# Adafruit_Motor_HAT_rev_A.net
KiCad netlist of a schematic drawn in EAGLE
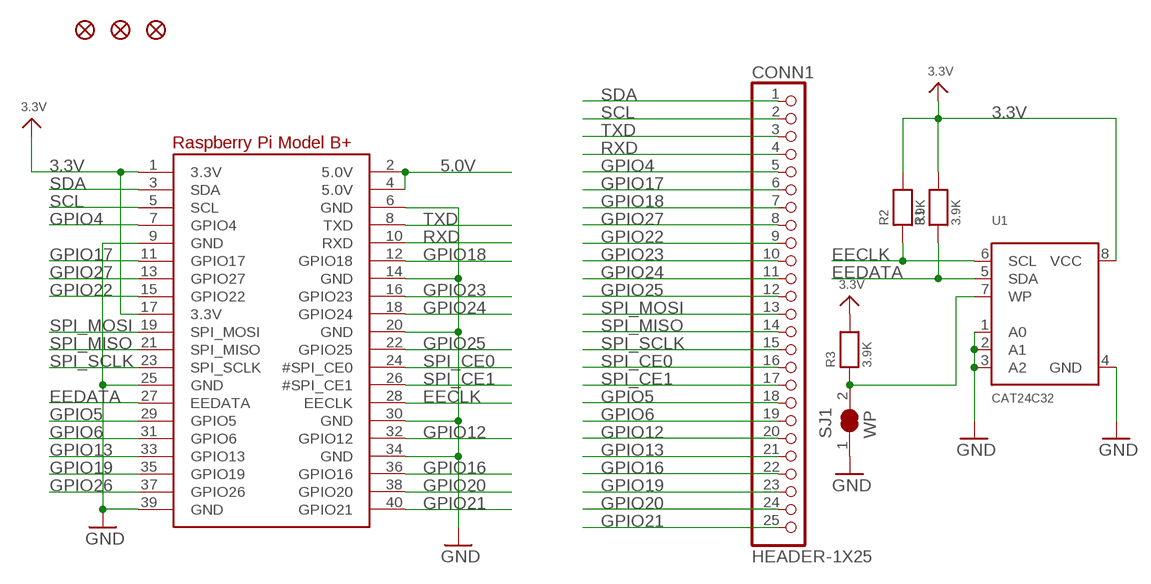
[diagram p0: schematic, sheet 1]
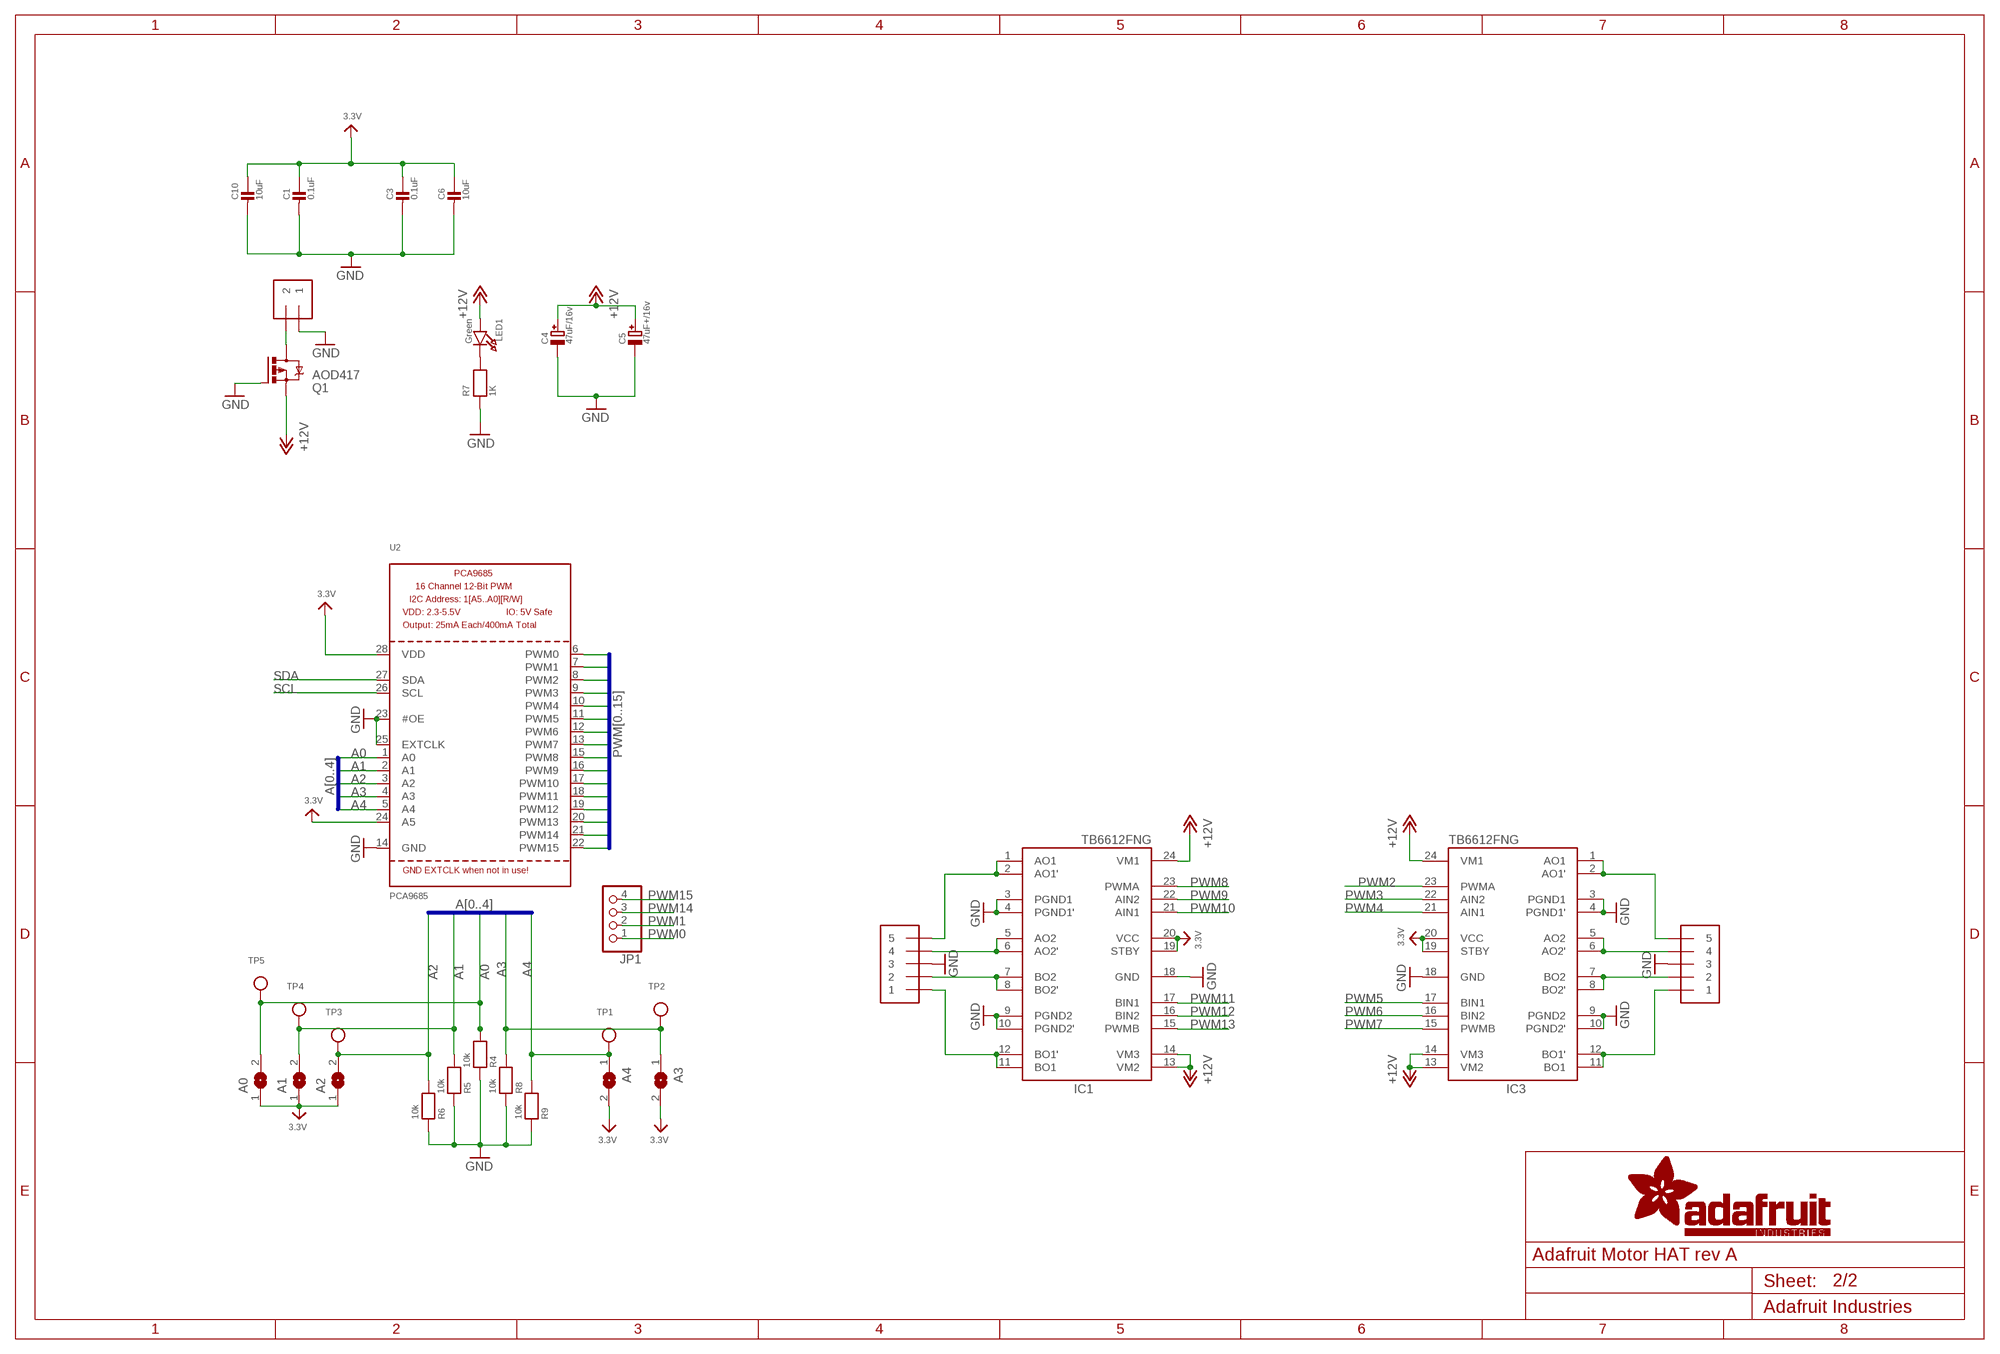
[diagram p1: schematic, sheet 2]

(export (version "E")
  (design (tool "Eeschema 10.0.6"))
  (components
    (comp (ref "CONN1")
      (value "HEADER-1X25")
      (footprint "eagle-import:1X25_ROUND_70MIL")
      (libsource (lib "eagle-import") (part "HEADER-1X25"))
    )
    (comp (ref "FID1")
      (value "FIDUCIAL\"\"")
      (footprint "eagle-import:FIDUCIAL_1MM")
      (libsource (lib "eagle-import") (part "FIDUCIAL{dblquote}{dblquote}"))
    )
    (comp (ref "FID2")
      (value "FIDUCIAL\"\"")
      (footprint "eagle-import:FIDUCIAL_1MM")
      (libsource (lib "eagle-import") (part "FIDUCIAL{dblquote}{dblquote}"))
    )
    (comp (ref "FID3")
      (value "FIDUCIAL\"\"")
      (footprint "eagle-import:FIDUCIAL_1MM")
      (libsource (lib "eagle-import") (part "FIDUCIAL{dblquote}{dblquote}"))
    )
    (comp (ref "R1")
      (value "3.9K")
      (footprint "eagle-import:0805-NO")
      (libsource (lib "eagle-import") (part "RESISTOR0805_NOOUTLINE"))
    )
    (comp (ref "R2")
      (value "3.9K")
      (footprint "eagle-import:0805-NO")
      (libsource (lib "eagle-import") (part "RESISTOR0805_NOOUTLINE"))
    )
    (comp (ref "R3")
      (value "3.9K")
      (footprint "eagle-import:0805-NO")
      (libsource (lib "eagle-import") (part "RESISTOR0805_NOOUTLINE"))
    )
    (comp (ref "RPI1")
      (value "RASPBERRYPI_BPLUS_HATSLOTS")
      (footprint "eagle-import:PI_HAT_SLOTS")
      (libsource (lib "eagle-import") (part "RASPBERRYPI_BPLUS_HATSLOTS"))
    )
    (comp (ref "SJ1")
      (value "WP")
      (footprint "eagle-import:SOLDERJUMPER_CLOSEDWIRE")
      (libsource (lib "eagle-import") (part "SOLDERJUMPER_CLOSED"))
    )
    (comp (ref "U1")
      (value "CAT24C32")
      (footprint "eagle-import:SOIC8_150MIL")
      (libsource (lib "eagle-import") (part "EEPROM_I2C_SOIC8_GENERIC"))
    )
    (comp (ref "A0")
      (value "SOLDERJUMPERREFLOW_NOPASTE")
      (footprint "eagle-import:SOLDERJUMPER_REFLOW_NOPASTE")
      (libsource (lib "eagle-import") (part "SOLDERJUMPERREFLOW_NOPASTE"))
    )
    (comp (ref "A1")
      (value "SOLDERJUMPERREFLOW_NOPASTE")
      (footprint "eagle-import:SOLDERJUMPER_REFLOW_NOPASTE")
      (libsource (lib "eagle-import") (part "SOLDERJUMPERREFLOW_NOPASTE"))
    )
    (comp (ref "A2")
      (value "SOLDERJUMPERREFLOW_NOPASTE")
      (footprint "eagle-import:SOLDERJUMPER_REFLOW_NOPASTE")
      (libsource (lib "eagle-import") (part "SOLDERJUMPERREFLOW_NOPASTE"))
    )
    (comp (ref "A3")
      (value "SOLDERJUMPERREFLOW_NOPASTE")
      (footprint "eagle-import:SOLDERJUMPER_REFLOW_NOPASTE")
      (libsource (lib "eagle-import") (part "SOLDERJUMPERREFLOW_NOPASTE"))
    )
    (comp (ref "A4")
      (value "SOLDERJUMPERREFLOW_NOPASTE")
      (footprint "eagle-import:SOLDERJUMPER_REFLOW_NOPASTE")
      (libsource (lib "eagle-import") (part "SOLDERJUMPERREFLOW_NOPASTE"))
    )
    (comp (ref "C1")
      (value "0.1uF")
      (footprint "eagle-import:0805-NO")
      (libsource (lib "eagle-import") (part "CAP_CERAMIC0805-NOOUTLINE"))
    )
    (comp (ref "C3")
      (value "0.1uF")
      (footprint "eagle-import:0805-NO")
      (libsource (lib "eagle-import") (part "CAP_CERAMIC0805-NOOUTLINE"))
    )
    (comp (ref "C4")
      (value "47uF/16v")
      (footprint "eagle-import:PANASONIC_C")
      (libsource (lib "eagle-import") (part "CAP_ELECTROLYTICPANASONIC_C"))
    )
    (comp (ref "C5")
      (value "47uF+/16v")
      (footprint "eagle-import:PANASONIC_C")
      (libsource (lib "eagle-import") (part "CAP_ELECTROLYTICPANASONIC_C"))
    )
    (comp (ref "C6")
      (value "10uF")
      (footprint "eagle-import:0805-NO")
      (libsource (lib "eagle-import") (part "CAP_CERAMIC0805-NOOUTLINE"))
    )
    (comp (ref "C10")
      (value "10uF")
      (footprint "eagle-import:0805-NO")
      (libsource (lib "eagle-import") (part "CAP_CERAMIC0805-NOOUTLINE"))
    )
    (comp (ref "IC1")
      (value "TB6612FNG")
      (footprint "eagle-import:SSOP24")
      (libsource (lib "eagle-import") (part "TB6612FNG"))
    )
    (comp (ref "IC3")
      (value "TB6612FNG")
      (footprint "eagle-import:SSOP24")
      (libsource (lib "eagle-import") (part "TB6612FNG"))
    )
    (comp (ref "J1")
      (value "1X5")
      (footprint "eagle-import:1X05-3.5MM")
      (libsource (lib "eagle-import") (part "1X5"))
    )
    (comp (ref "J3")
      (value "1X5")
      (footprint "eagle-import:1X05-3.5MM")
      (libsource (lib "eagle-import") (part "1X5"))
    )
    (comp (ref "JP1")
      (value "HEADER-1X476MIL")
      (footprint "eagle-import:1X04_ROUND_76")
      (libsource (lib "eagle-import") (part "HEADER-1X476MIL"))
    )
    (comp (ref "LED1")
      (value "Green")
      (footprint "eagle-import:CHIPLED_0805_NOOUTLINE")
      (libsource (lib "eagle-import") (part "LED0805_NOOUTLINE"))
    )
    (comp (ref "MPOWER")
      (value "1X2-3.5MM")
      (footprint "eagle-import:1X2-3.5MM")
      (libsource (lib "eagle-import") (part "1X2-3.5MM"))
    )
    (comp (ref "Q1")
      (value "AOD417")
      (footprint "eagle-import:D-PAK_TO252AA")
      (libsource (lib "eagle-import") (part "IRF?5305R"))
    )
    (comp (ref "R4")
      (value "10k")
      (footprint "eagle-import:0805-NO")
      (libsource (lib "eagle-import") (part "RESISTOR0805_NOOUTLINE"))
    )
    (comp (ref "R5")
      (value "10k")
      (footprint "eagle-import:0805-NO")
      (libsource (lib "eagle-import") (part "RESISTOR0805_NOOUTLINE"))
    )
    (comp (ref "R6")
      (value "10k")
      (footprint "eagle-import:0805-NO")
      (libsource (lib "eagle-import") (part "RESISTOR0805_NOOUTLINE"))
    )
    (comp (ref "R7")
      (value "1K")
      (footprint "eagle-import:0805-NO")
      (libsource (lib "eagle-import") (part "RESISTOR0805_NOOUTLINE"))
    )
    (comp (ref "R8")
      (value "10k")
      (footprint "eagle-import:0805-NO")
      (libsource (lib "eagle-import") (part "RESISTOR0805_NOOUTLINE"))
    )
    (comp (ref "R9")
      (value "10k")
      (footprint "eagle-import:0805-NO")
      (libsource (lib "eagle-import") (part "RESISTOR0805_NOOUTLINE"))
    )
    (comp (ref "TP1")
      (value "TESTPOINTROUND2MM")
      (footprint "eagle-import:TESTPOINT_ROUND_2MM")
      (libsource (lib "eagle-import") (part "TESTPOINTROUND2MM"))
    )
    (comp (ref "TP2")
      (value "TESTPOINTROUND2MM")
      (footprint "eagle-import:TESTPOINT_ROUND_2MM")
      (libsource (lib "eagle-import") (part "TESTPOINTROUND2MM"))
    )
    (comp (ref "TP3")
      (value "TESTPOINTROUND2MM")
      (footprint "eagle-import:TESTPOINT_ROUND_2MM")
      (libsource (lib "eagle-import") (part "TESTPOINTROUND2MM"))
    )
    (comp (ref "TP4")
      (value "TESTPOINTROUND2MM")
      (footprint "eagle-import:TESTPOINT_ROUND_2MM")
      (libsource (lib "eagle-import") (part "TESTPOINTROUND2MM"))
    )
    (comp (ref "TP5")
      (value "TESTPOINTROUND2MM")
      (footprint "eagle-import:TESTPOINT_ROUND_2MM")
      (libsource (lib "eagle-import") (part "TESTPOINTROUND2MM"))
    )
    (comp (ref "U2")
      (value "PCA9685")
      (footprint "eagle-import:TSSOP28")
      (libsource (lib "eagle-import") (part "PCA9685"))
    )
  )
  (nets
    (net (code "1") (name "+12V") (class "Default")
      (node (ref "C4") (pin "+") (pinfunction "+_+") (pintype "passive"))
      (node (ref "C5") (pin "+") (pinfunction "+_+") (pintype "passive"))
      (node (ref "IC1") (pin "13") (pinfunction "VM2_13") (pintype "power_in"))
      (node (ref "IC1") (pin "14") (pinfunction "VM3_14") (pintype "power_in"))
      (node (ref "IC1") (pin "24") (pinfunction "VM1_24") (pintype "power_in"))
      (node (ref "IC3") (pin "13") (pinfunction "VM2_13") (pintype "power_in"))
      (node (ref "IC3") (pin "14") (pinfunction "VM3_14") (pintype "power_in"))
      (node (ref "IC3") (pin "24") (pinfunction "VM1_24") (pintype "power_in"))
      (node (ref "LED1") (pin "A") (pinfunction "A_A") (pintype "passive"))
      (node (ref "Q1") (pin "3") (pinfunction "S_3") (pintype "passive"))
    )
    (net (code "4") (name "3.3V") (class "Default")
      (node (ref "A0") (pin "1") (pinfunction "1_1") (pintype "passive"))
      (node (ref "A1") (pin "1") (pinfunction "1_1") (pintype "passive"))
      (node (ref "A2") (pin "1") (pinfunction "1_1") (pintype "passive"))
      (node (ref "A3") (pin "2") (pinfunction "2_2") (pintype "passive"))
      (node (ref "A4") (pin "2") (pinfunction "2_2") (pintype "passive"))
      (node (ref "C1") (pin "1") (pinfunction "1_1") (pintype "passive"))
      (node (ref "C10") (pin "1") (pinfunction "1_1") (pintype "passive"))
      (node (ref "C3") (pin "1") (pinfunction "1_1") (pintype "passive"))
      (node (ref "C6") (pin "1") (pinfunction "1_1") (pintype "passive"))
      (node (ref "IC1") (pin "19") (pinfunction "STBY_19") (pintype "input"))
      (node (ref "IC1") (pin "20") (pinfunction "VCC_20") (pintype "power_in"))
      (node (ref "IC3") (pin "19") (pinfunction "STBY_19") (pintype "input"))
      (node (ref "IC3") (pin "20") (pinfunction "VCC_20") (pintype "power_in"))
      (node (ref "R1") (pin "2") (pinfunction "2_2") (pintype "passive"))
      (node (ref "R2") (pin "2") (pinfunction "2_2") (pintype "passive"))
      (node (ref "R3") (pin "2") (pinfunction "2_2") (pintype "passive"))
      (node (ref "RPI1") (pin "1") (pinfunction "3.3V_1") (pintype "power_in"))
      (node (ref "RPI1") (pin "17") (pinfunction "3.3V_17") (pintype "power_in"))
      (node (ref "U1") (pin "8") (pinfunction "VCC_8") (pintype "power_in"))
      (node (ref "U2") (pin "24") (pinfunction "A5_24") (pintype "bidirectional"))
      (node (ref "U2") (pin "28") (pinfunction "VDD_28") (pintype "power_in"))
    )
    (net (code "5") (name "5.0V") (class "Default")
      (node (ref "RPI1") (pin "2") (pinfunction "5.0V_2") (pintype "power_in"))
      (node (ref "RPI1") (pin "4") (pinfunction "5.0V_4") (pintype "power_in"))
    )
    (net (code "6") (name "A0") (class "Default")
      (node (ref "A0") (pin "2") (pinfunction "2_2") (pintype "passive"))
      (node (ref "R4") (pin "2") (pinfunction "2_2") (pintype "passive"))
      (node (ref "TP5") (pin "P$1") (pinfunction "P$1_P$1") (pintype "bidirectional"))
      (node (ref "U2") (pin "1") (pinfunction "A0_1") (pintype "bidirectional"))
    )
    (net (code "7") (name "A1") (class "Default")
      (node (ref "A1") (pin "2") (pinfunction "2_2") (pintype "passive"))
      (node (ref "R5") (pin "2") (pinfunction "2_2") (pintype "passive"))
      (node (ref "TP4") (pin "P$1") (pinfunction "P$1_P$1") (pintype "bidirectional"))
      (node (ref "U2") (pin "2") (pinfunction "A1_2") (pintype "bidirectional"))
    )
    (net (code "8") (name "A2") (class "Default")
      (node (ref "A2") (pin "2") (pinfunction "2_2") (pintype "passive"))
      (node (ref "R6") (pin "2") (pinfunction "2_2") (pintype "passive"))
      (node (ref "TP3") (pin "P$1") (pinfunction "P$1_P$1") (pintype "bidirectional"))
      (node (ref "U2") (pin "3") (pinfunction "A2_3") (pintype "bidirectional"))
    )
    (net (code "9") (name "A3") (class "Default")
      (node (ref "A3") (pin "1") (pinfunction "1_1") (pintype "passive"))
      (node (ref "R8") (pin "2") (pinfunction "2_2") (pintype "passive"))
      (node (ref "TP2") (pin "P$1") (pinfunction "P$1_P$1") (pintype "bidirectional"))
      (node (ref "U2") (pin "4") (pinfunction "A3_4") (pintype "bidirectional"))
    )
    (net (code "10") (name "A4") (class "Default")
      (node (ref "A4") (pin "1") (pinfunction "1_1") (pintype "passive"))
      (node (ref "R9") (pin "2") (pinfunction "2_2") (pintype "passive"))
      (node (ref "TP1") (pin "P$1") (pinfunction "P$1_P$1") (pintype "bidirectional"))
      (node (ref "U2") (pin "5") (pinfunction "A4_5") (pintype "bidirectional"))
    )
    (net (code "11") (name "EECLK") (class "Default")
      (node (ref "R2") (pin "1") (pinfunction "1_1") (pintype "passive"))
      (node (ref "RPI1") (pin "28") (pinfunction "EECLK_28") (pintype "power_in"))
      (node (ref "U1") (pin "6") (pinfunction "SCL_6") (pintype "input"))
    )
    (net (code "12") (name "EEDATA") (class "Default")
      (node (ref "R1") (pin "1") (pinfunction "1_1") (pintype "passive"))
      (node (ref "RPI1") (pin "27") (pinfunction "EEDATA_27") (pintype "bidirectional"))
      (node (ref "U1") (pin "5") (pinfunction "SDA_5") (pintype "bidirectional"))
    )
    (net (code "13") (name "GND") (class "Default")
      (node (ref "C1") (pin "2") (pinfunction "2_2") (pintype "passive"))
      (node (ref "C10") (pin "2") (pinfunction "2_2") (pintype "passive"))
      (node (ref "C3") (pin "2") (pinfunction "2_2") (pintype "passive"))
      (node (ref "C4") (pin "-") (pinfunction "-_-") (pintype "passive"))
      (node (ref "C5") (pin "-") (pinfunction "-_-") (pintype "passive"))
      (node (ref "C6") (pin "2") (pinfunction "2_2") (pintype "passive"))
      (node (ref "IC1") (pin "10") (pinfunction "PGND2'_10") (pintype "power_in"))
      (node (ref "IC1") (pin "18") (pinfunction "GND_18") (pintype "power_in"))
      (node (ref "IC1") (pin "3") (pinfunction "PGND1_3") (pintype "power_in"))
      (node (ref "IC1") (pin "4") (pinfunction "PGND1'_4") (pintype "power_in"))
      (node (ref "IC1") (pin "9") (pinfunction "PGND2_9") (pintype "power_in"))
      (node (ref "IC3") (pin "10") (pinfunction "PGND2'_10") (pintype "power_in"))
      (node (ref "IC3") (pin "18") (pinfunction "GND_18") (pintype "power_in"))
      (node (ref "IC3") (pin "3") (pinfunction "PGND1_3") (pintype "power_in"))
      (node (ref "IC3") (pin "4") (pinfunction "PGND1'_4") (pintype "power_in"))
      (node (ref "IC3") (pin "9") (pinfunction "PGND2_9") (pintype "power_in"))
      (node (ref "J1") (pin "3") (pinfunction "3_3") (pintype "passive"))
      (node (ref "J3") (pin "3") (pinfunction "3_3") (pintype "passive"))
      (node (ref "MPOWER") (pin "1") (pinfunction "1_1") (pintype "passive"))
      (node (ref "Q1") (pin "1") (pinfunction "G_1") (pintype "passive"))
      (node (ref "R4") (pin "1") (pinfunction "1_1") (pintype "passive"))
      (node (ref "R5") (pin "1") (pinfunction "1_1") (pintype "passive"))
      (node (ref "R6") (pin "1") (pinfunction "1_1") (pintype "passive"))
      (node (ref "R7") (pin "1") (pinfunction "1_1") (pintype "passive"))
      (node (ref "R8") (pin "1") (pinfunction "1_1") (pintype "passive"))
      (node (ref "R9") (pin "1") (pinfunction "1_1") (pintype "passive"))
      (node (ref "RPI1") (pin "14") (pinfunction "GND_14") (pintype "power_in"))
      (node (ref "RPI1") (pin "20") (pinfunction "GND_20") (pintype "power_in"))
      (node (ref "RPI1") (pin "25") (pinfunction "GND_25") (pintype "power_in"))
      (node (ref "RPI1") (pin "30") (pinfunction "GND_30") (pintype "bidirectional"))
      (node (ref "RPI1") (pin "34") (pinfunction "GND_34") (pintype "bidirectional"))
      (node (ref "RPI1") (pin "39") (pinfunction "GND_39") (pintype "power_in"))
      (node (ref "RPI1") (pin "6") (pinfunction "GND_6") (pintype "power_in"))
      (node (ref "RPI1") (pin "9") (pinfunction "GND_9") (pintype "power_in"))
      (node (ref "SJ1") (pin "1") (pinfunction "1_1") (pintype "passive"))
      (node (ref "U1") (pin "1") (pinfunction "A0_1") (pintype "input"))
      (node (ref "U1") (pin "2") (pinfunction "A1_2") (pintype "input"))
      (node (ref "U1") (pin "3") (pinfunction "A2_3") (pintype "input"))
      (node (ref "U1") (pin "4") (pinfunction "GND_4") (pintype "power_in"))
      (node (ref "U2") (pin "14") (pinfunction "GND_14") (pintype "power_in"))
      (node (ref "U2") (pin "23") (pinfunction "#OE_23") (pintype "input"))
      (node (ref "U2") (pin "25") (pinfunction "EXTCLK_25") (pintype "input"))
    )
    (net (code "14") (name "GPIO4") (class "Default")
      (node (ref "CONN1") (pin "5") (pinfunction "5_5") (pintype "passive"))
      (node (ref "RPI1") (pin "7") (pinfunction "GPIO4_7") (pintype "bidirectional"))
    )
    (net (code "15") (name "GPIO5") (class "Default")
      (node (ref "CONN1") (pin "18") (pinfunction "18_18") (pintype "passive"))
      (node (ref "RPI1") (pin "29") (pinfunction "GPIO5_29") (pintype "bidirectional"))
    )
    (net (code "16") (name "GPIO6") (class "Default")
      (node (ref "CONN1") (pin "19") (pinfunction "19_19") (pintype "passive"))
      (node (ref "RPI1") (pin "31") (pinfunction "GPIO6_31") (pintype "power_in"))
    )
    (net (code "17") (name "GPIO12") (class "Default")
      (node (ref "CONN1") (pin "20") (pinfunction "20_20") (pintype "passive"))
      (node (ref "RPI1") (pin "32") (pinfunction "GPIO12_32") (pintype "bidirectional"))
    )
    (net (code "18") (name "GPIO13") (class "Default")
      (node (ref "CONN1") (pin "21") (pinfunction "21_21") (pintype "passive"))
      (node (ref "RPI1") (pin "33") (pinfunction "GPIO13_33") (pintype "bidirectional"))
    )
    (net (code "19") (name "GPIO16") (class "Default")
      (node (ref "CONN1") (pin "22") (pinfunction "22_22") (pintype "passive"))
      (node (ref "RPI1") (pin "36") (pinfunction "GPIO16_36") (pintype "power_in"))
    )
    (net (code "20") (name "GPIO17") (class "Default")
      (node (ref "CONN1") (pin "6") (pinfunction "6_6") (pintype "passive"))
      (node (ref "RPI1") (pin "11") (pinfunction "GPIO17_11") (pintype "bidirectional"))
    )
    (net (code "21") (name "GPIO18") (class "Default")
      (node (ref "CONN1") (pin "7") (pinfunction "7_7") (pintype "passive"))
      (node (ref "RPI1") (pin "12") (pinfunction "GPIO18_12") (pintype "bidirectional"))
    )
    (net (code "22") (name "GPIO19") (class "Default")
      (node (ref "CONN1") (pin "23") (pinfunction "23_23") (pintype "passive"))
      (node (ref "RPI1") (pin "35") (pinfunction "GPIO19_35") (pintype "bidirectional"))
    )
    (net (code "23") (name "GPIO20") (class "Default")
      (node (ref "CONN1") (pin "24") (pinfunction "24_24") (pintype "passive"))
      (node (ref "RPI1") (pin "38") (pinfunction "GPIO20_38") (pintype "bidirectional"))
    )
    (net (code "24") (name "GPIO21") (class "Default")
      (node (ref "CONN1") (pin "25") (pinfunction "25_25") (pintype "passive"))
      (node (ref "RPI1") (pin "40") (pinfunction "GPIO21_40") (pintype "bidirectional"))
    )
    (net (code "25") (name "GPIO22") (class "Default")
      (node (ref "CONN1") (pin "9") (pinfunction "9_9") (pintype "passive"))
      (node (ref "RPI1") (pin "15") (pinfunction "GPIO22_15") (pintype "bidirectional"))
    )
    (net (code "26") (name "GPIO23") (class "Default")
      (node (ref "CONN1") (pin "10") (pinfunction "10_10") (pintype "passive"))
      (node (ref "RPI1") (pin "16") (pinfunction "GPIO23_16") (pintype "bidirectional"))
    )
    (net (code "27") (name "GPIO24") (class "Default")
      (node (ref "CONN1") (pin "11") (pinfunction "11_11") (pintype "passive"))
      (node (ref "RPI1") (pin "18") (pinfunction "GPIO24_18") (pintype "bidirectional"))
    )
    (net (code "28") (name "GPIO25") (class "Default")
      (node (ref "CONN1") (pin "12") (pinfunction "12_12") (pintype "passive"))
      (node (ref "RPI1") (pin "22") (pinfunction "GPIO25_22") (pintype "bidirectional"))
    )
    (net (code "29") (name "GPIO26") (class "Default")
      (node (ref "RPI1") (pin "37") (pinfunction "GPIO26_37") (pintype "bidirectional"))
    )
    (net (code "30") (name "GPIO27") (class "Default")
      (node (ref "CONN1") (pin "8") (pinfunction "8_8") (pintype "passive"))
      (node (ref "RPI1") (pin "13") (pinfunction "GPIO27_13") (pintype "bidirectional"))
    )
    (net (code "31") (name "Net-(IC1-AO1')") (class "Default")
      (node (ref "IC1") (pin "1") (pinfunction "AO1_1") (pintype "output"))
      (node (ref "IC1") (pin "2") (pinfunction "AO1'_2") (pintype "output"))
      (node (ref "J1") (pin "5") (pinfunction "5_5") (pintype "passive"))
    )
    (net (code "32") (name "Net-(IC1-AO2')") (class "Default")
      (node (ref "IC1") (pin "5") (pinfunction "AO2_5") (pintype "output"))
      (node (ref "IC1") (pin "6") (pinfunction "AO2'_6") (pintype "output"))
      (node (ref "J1") (pin "4") (pinfunction "4_4") (pintype "passive"))
    )
    (net (code "33") (name "Net-(IC1-BO1')") (class "Default")
      (node (ref "IC1") (pin "11") (pinfunction "BO1_11") (pintype "output"))
      (node (ref "IC1") (pin "12") (pinfunction "BO1'_12") (pintype "output"))
      (node (ref "J1") (pin "1") (pinfunction "1_1") (pintype "passive"))
    )
    (net (code "34") (name "Net-(IC1-BO2')") (class "Default")
      (node (ref "IC1") (pin "7") (pinfunction "BO2_7") (pintype "output"))
      (node (ref "IC1") (pin "8") (pinfunction "BO2'_8") (pintype "output"))
      (node (ref "J1") (pin "2") (pinfunction "2_2") (pintype "passive"))
    )
    (net (code "35") (name "Net-(IC3-AO1')") (class "Default")
      (node (ref "IC3") (pin "1") (pinfunction "AO1_1") (pintype "output"))
      (node (ref "IC3") (pin "2") (pinfunction "AO1'_2") (pintype "output"))
      (node (ref "J3") (pin "5") (pinfunction "5_5") (pintype "passive"))
    )
    (net (code "36") (name "Net-(IC3-AO2')") (class "Default")
      (node (ref "IC3") (pin "5") (pinfunction "AO2_5") (pintype "output"))
      (node (ref "IC3") (pin "6") (pinfunction "AO2'_6") (pintype "output"))
      (node (ref "J3") (pin "4") (pinfunction "4_4") (pintype "passive"))
    )
    (net (code "37") (name "Net-(IC3-BO1')") (class "Default")
      (node (ref "IC3") (pin "11") (pinfunction "BO1_11") (pintype "output"))
      (node (ref "IC3") (pin "12") (pinfunction "BO1'_12") (pintype "output"))
      (node (ref "J3") (pin "1") (pinfunction "1_1") (pintype "passive"))
    )
    (net (code "38") (name "Net-(IC3-BO2')") (class "Default")
      (node (ref "IC3") (pin "7") (pinfunction "BO2_7") (pintype "output"))
      (node (ref "IC3") (pin "8") (pinfunction "BO2'_8") (pintype "output"))
      (node (ref "J3") (pin "2") (pinfunction "2_2") (pintype "passive"))
    )
    (net (code "39") (name "Net-(LED1-PadC)") (class "Default")
      (node (ref "LED1") (pin "C") (pinfunction "C_C") (pintype "passive"))
      (node (ref "R7") (pin "2") (pinfunction "2_2") (pintype "passive"))
    )
    (net (code "40") (name "Net-(Q1-D)") (class "Default")
      (node (ref "MPOWER") (pin "2") (pinfunction "2_2") (pintype "passive"))
      (node (ref "Q1") (pin "4") (pinfunction "D_4") (pintype "passive"))
    )
    (net (code "41") (name "Net-(U1-WP)") (class "Default")
      (node (ref "R3") (pin "1") (pinfunction "1_1") (pintype "passive"))
      (node (ref "SJ1") (pin "2") (pinfunction "2_2") (pintype "passive"))
      (node (ref "U1") (pin "7") (pinfunction "WP_7") (pintype "input"))
    )
    (net (code "42") (name "PWM0") (class "Default")
      (node (ref "JP1") (pin "1") (pinfunction "1_1") (pintype "passive"))
      (node (ref "U2") (pin "6") (pinfunction "PWM0_6") (pintype "output"))
    )
    (net (code "43") (name "PWM1") (class "Default")
      (node (ref "JP1") (pin "2") (pinfunction "2_2") (pintype "passive"))
      (node (ref "U2") (pin "7") (pinfunction "PWM1_7") (pintype "output"))
    )
    (net (code "44") (name "PWM2") (class "Default")
      (node (ref "IC3") (pin "23") (pinfunction "PWMA_23") (pintype "input"))
      (node (ref "U2") (pin "8") (pinfunction "PWM2_8") (pintype "output"))
    )
    (net (code "45") (name "PWM3") (class "Default")
      (node (ref "IC3") (pin "22") (pinfunction "AIN2_22") (pintype "input"))
      (node (ref "U2") (pin "9") (pinfunction "PWM3_9") (pintype "output"))
    )
    (net (code "46") (name "PWM4") (class "Default")
      (node (ref "IC3") (pin "21") (pinfunction "AIN1_21") (pintype "input"))
      (node (ref "U2") (pin "10") (pinfunction "PWM4_10") (pintype "output"))
    )
    (net (code "47") (name "PWM5") (class "Default")
      (node (ref "IC3") (pin "17") (pinfunction "BIN1_17") (pintype "input"))
      (node (ref "U2") (pin "11") (pinfunction "PWM5_11") (pintype "output"))
    )
    (net (code "48") (name "PWM6") (class "Default")
      (node (ref "IC3") (pin "16") (pinfunction "BIN2_16") (pintype "input"))
      (node (ref "U2") (pin "12") (pinfunction "PWM6_12") (pintype "output"))
    )
    (net (code "49") (name "PWM7") (class "Default")
      (node (ref "IC3") (pin "15") (pinfunction "PWMB_15") (pintype "input"))
      (node (ref "U2") (pin "13") (pinfunction "PWM7_13") (pintype "output"))
    )
    (net (code "50") (name "PWM8") (class "Default")
      (node (ref "IC1") (pin "23") (pinfunction "PWMA_23") (pintype "input"))
      (node (ref "U2") (pin "15") (pinfunction "PWM8_15") (pintype "output"))
    )
    (net (code "51") (name "PWM9") (class "Default")
      (node (ref "IC1") (pin "22") (pinfunction "AIN2_22") (pintype "input"))
      (node (ref "U2") (pin "16") (pinfunction "PWM9_16") (pintype "output"))
    )
    (net (code "52") (name "PWM10") (class "Default")
      (node (ref "IC1") (pin "21") (pinfunction "AIN1_21") (pintype "input"))
      (node (ref "U2") (pin "17") (pinfunction "PWM10_17") (pintype "output"))
    )
    (net (code "53") (name "PWM11") (class "Default")
      (node (ref "IC1") (pin "17") (pinfunction "BIN1_17") (pintype "input"))
      (node (ref "U2") (pin "18") (pinfunction "PWM11_18") (pintype "output"))
    )
    (net (code "54") (name "PWM12") (class "Default")
      (node (ref "IC1") (pin "16") (pinfunction "BIN2_16") (pintype "input"))
      (node (ref "U2") (pin "19") (pinfunction "PWM12_19") (pintype "output"))
    )
    (net (code "55") (name "PWM13") (class "Default")
      (node (ref "IC1") (pin "15") (pinfunction "PWMB_15") (pintype "input"))
      (node (ref "U2") (pin "20") (pinfunction "PWM13_20") (pintype "output"))
    )
    (net (code "56") (name "PWM14") (class "Default")
      (node (ref "JP1") (pin "3") (pinfunction "3_3") (pintype "passive"))
      (node (ref "U2") (pin "21") (pinfunction "PWM14_21") (pintype "output"))
    )
    (net (code "57") (name "PWM15") (class "Default")
      (node (ref "JP1") (pin "4") (pinfunction "4_4") (pintype "passive"))
      (node (ref "U2") (pin "22") (pinfunction "PWM15_22") (pintype "output"))
    )
    (net (code "58") (name "RXD") (class "Default")
      (node (ref "CONN1") (pin "4") (pinfunction "4_4") (pintype "passive"))
      (node (ref "RPI1") (pin "10") (pinfunction "RXD_10") (pintype "bidirectional"))
    )
    (net (code "59") (name "SCL") (class "Default")
      (node (ref "CONN1") (pin "2") (pinfunction "2_2") (pintype "passive"))
      (node (ref "RPI1") (pin "5") (pinfunction "SCL_5") (pintype "bidirectional"))
      (node (ref "U2") (pin "26") (pinfunction "SCL_26") (pintype "bidirectional"))
    )
    (net (code "60") (name "SDA") (class "Default")
      (node (ref "CONN1") (pin "1") (pinfunction "1_1") (pintype "passive"))
      (node (ref "RPI1") (pin "3") (pinfunction "SDA_3") (pintype "bidirectional"))
      (node (ref "U2") (pin "27") (pinfunction "SDA_27") (pintype "bidirectional"))
    )
    (net (code "61") (name "SPI_CE0") (class "Default")
      (node (ref "CONN1") (pin "16") (pinfunction "16_16") (pintype "passive"))
      (node (ref "RPI1") (pin "24") (pinfunction "#SPI_CE0_24") (pintype "bidirectional"))
    )
    (net (code "62") (name "SPI_CE1") (class "Default")
      (node (ref "CONN1") (pin "17") (pinfunction "17_17") (pintype "passive"))
      (node (ref "RPI1") (pin "26") (pinfunction "#SPI_CE1_26") (pintype "bidirectional"))
    )
    (net (code "63") (name "SPI_MISO") (class "Default")
      (node (ref "CONN1") (pin "14") (pinfunction "14_14") (pintype "passive"))
      (node (ref "RPI1") (pin "21") (pinfunction "SPI_MISO_21") (pintype "bidirectional"))
    )
    (net (code "64") (name "SPI_MOSI") (class "Default")
      (node (ref "CONN1") (pin "13") (pinfunction "13_13") (pintype "passive"))
      (node (ref "RPI1") (pin "19") (pinfunction "SPI_MOSI_19") (pintype "bidirectional"))
    )
    (net (code "65") (name "SPI_SCLK") (class "Default")
      (node (ref "CONN1") (pin "15") (pinfunction "15_15") (pintype "passive"))
      (node (ref "RPI1") (pin "23") (pinfunction "SPI_SCLK_23") (pintype "bidirectional"))
    )
    (net (code "66") (name "TXD") (class "Default")
      (node (ref "CONN1") (pin "3") (pinfunction "3_3") (pintype "passive"))
      (node (ref "RPI1") (pin "8") (pinfunction "TXD_8") (pintype "output"))
    )
  )
)
